# Impedance_analyzer.net
KiCad netlist of a schematic drawn in EAGLE
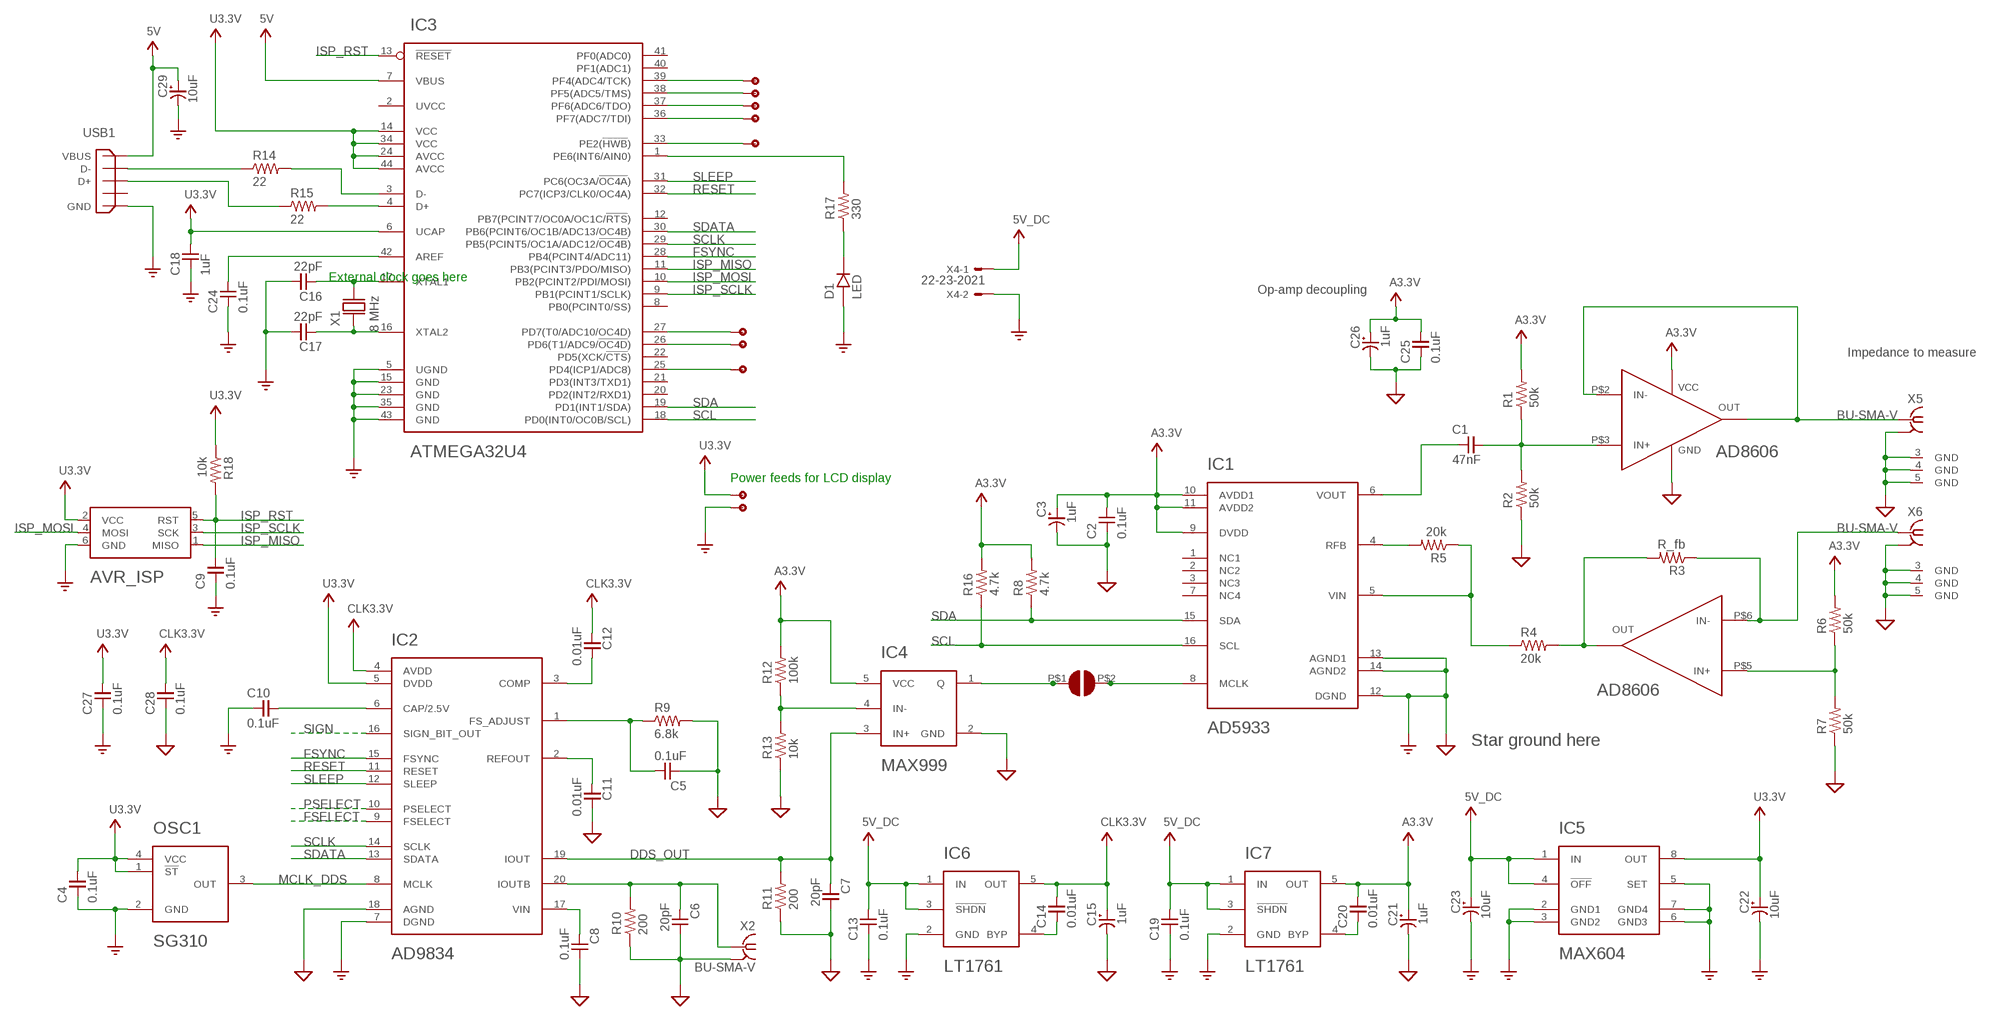
[diagram p0: schematic, sheet 1]

(export (version "E")
  (design (tool "Eeschema 10.0.6"))
  (components
    (comp (ref "C1")
      (value "47nF")
      (footprint "eagle-import:0805")
      (libsource (lib "eagle-import") (part "CAPACITOR0805"))
    )
    (comp (ref "C2")
      (value "0.1uF")
      (footprint "eagle-import:0805")
      (libsource (lib "eagle-import") (part "CAPACITOR0805"))
    )
    (comp (ref "C3")
      (value "1uF")
      (footprint "eagle-import:1206")
      (libsource (lib "eagle-import") (part "CAPACITOR+"))
    )
    (comp (ref "C4")
      (value "0.1uF")
      (footprint "eagle-import:0805")
      (libsource (lib "eagle-import") (part "CAPACITOR0805"))
    )
    (comp (ref "C5")
      (value "0.1uF")
      (footprint "eagle-import:0805")
      (libsource (lib "eagle-import") (part "CAPACITOR0805"))
    )
    (comp (ref "C6")
      (value "20pF")
      (footprint "eagle-import:0805")
      (libsource (lib "eagle-import") (part "CAPACITOR0805"))
    )
    (comp (ref "C7")
      (value "20pF")
      (footprint "eagle-import:0805")
      (libsource (lib "eagle-import") (part "CAPACITOR0805"))
    )
    (comp (ref "C8")
      (value "0.1uF")
      (footprint "eagle-import:0805")
      (libsource (lib "eagle-import") (part "CAPACITOR0805"))
    )
    (comp (ref "C9")
      (value "0.1uF")
      (footprint "eagle-import:0805")
      (libsource (lib "eagle-import") (part "CAPACITOR0805"))
    )
    (comp (ref "C10")
      (value "0.1uF")
      (footprint "eagle-import:0805")
      (libsource (lib "eagle-import") (part "CAPACITOR0805"))
    )
    (comp (ref "C11")
      (value "0.01uF")
      (footprint "eagle-import:0805")
      (libsource (lib "eagle-import") (part "CAPACITOR0805"))
    )
    (comp (ref "C12")
      (value "0.01uF")
      (footprint "eagle-import:0805")
      (libsource (lib "eagle-import") (part "CAPACITOR0805"))
    )
    (comp (ref "C13")
      (value "0.1uF")
      (footprint "eagle-import:0805")
      (libsource (lib "eagle-import") (part "CAPACITOR0805"))
    )
    (comp (ref "C14")
      (value "0.01uF")
      (footprint "eagle-import:0805")
      (libsource (lib "eagle-import") (part "CAPACITOR0805"))
    )
    (comp (ref "C15")
      (value "1uF")
      (footprint "eagle-import:1206")
      (libsource (lib "eagle-import") (part "CAPACITOR+"))
    )
    (comp (ref "C16")
      (value "22pF")
      (footprint "eagle-import:0805")
      (libsource (lib "eagle-import") (part "CAPACITOR0805"))
    )
    (comp (ref "C17")
      (value "22pF")
      (footprint "eagle-import:0805")
      (libsource (lib "eagle-import") (part "CAPACITOR0805"))
    )
    (comp (ref "C18")
      (value "1uF")
      (footprint "eagle-import:0805")
      (libsource (lib "eagle-import") (part "CAPACITOR0805"))
    )
    (comp (ref "C19")
      (value "0.1uF")
      (footprint "eagle-import:0805")
      (libsource (lib "eagle-import") (part "CAPACITOR0805"))
    )
    (comp (ref "C20")
      (value "0.01uF")
      (footprint "eagle-import:0805")
      (libsource (lib "eagle-import") (part "CAPACITOR0805"))
    )
    (comp (ref "C21")
      (value "1uF")
      (footprint "eagle-import:1206")
      (libsource (lib "eagle-import") (part "CAPACITOR+"))
    )
    (comp (ref "C22")
      (value "10uF")
      (footprint "eagle-import:1206")
      (libsource (lib "eagle-import") (part "CAPACITOR+"))
    )
    (comp (ref "C23")
      (value "10uF")
      (footprint "eagle-import:1206")
      (libsource (lib "eagle-import") (part "CAPACITOR+"))
    )
    (comp (ref "C24")
      (value "0.1uF")
      (footprint "eagle-import:0805")
      (libsource (lib "eagle-import") (part "CAPACITOR0805"))
    )
    (comp (ref "C25")
      (value "0.1uF")
      (footprint "eagle-import:0805")
      (libsource (lib "eagle-import") (part "CAPACITOR0805"))
    )
    (comp (ref "C26")
      (value "1uF")
      (footprint "eagle-import:1206")
      (libsource (lib "eagle-import") (part "CAPACITOR+"))
    )
    (comp (ref "C27")
      (value "0.1uF")
      (footprint "eagle-import:0805")
      (libsource (lib "eagle-import") (part "CAPACITOR0805"))
    )
    (comp (ref "C28")
      (value "0.1uF")
      (footprint "eagle-import:0805")
      (libsource (lib "eagle-import") (part "CAPACITOR0805"))
    )
    (comp (ref "C29")
      (value "10uF")
      (footprint "eagle-import:1206")
      (libsource (lib "eagle-import") (part "CAPACITOR+"))
    )
    (comp (ref "D1")
      (value "LED")
      (footprint "eagle-import:0805")
      (libsource (lib "eagle-import") (part "DIODE0805"))
    )
    (comp (ref "IC1")
      (value "AD5933")
      (footprint "eagle-import:SSOP_16")
      (libsource (lib "eagle-import") (part "AD5933"))
    )
    (comp (ref "IC2")
      (value "AD9834")
      (footprint "eagle-import:TSSOP_20")
      (libsource (lib "eagle-import") (part "AD9834"))
    )
    (comp (ref "IC3")
      (value "ATMEGA32U4")
      (footprint "eagle-import:TQFP_44")
      (libsource (lib "eagle-import") (part "ATMEGA32U4"))
    )
    (comp (ref "IC4")
      (value "MAX999")
      (footprint "eagle-import:SOT_23-5")
      (libsource (lib "eagle-import") (part "MAX999"))
    )
    (comp (ref "IC5")
      (value "MAX604")
      (footprint "eagle-import:SO_8")
      (libsource (lib "eagle-import") (part "MAX603"))
    )
    (comp (ref "IC6")
      (value "LT1761")
      (footprint "eagle-import:TSOT-23")
      (libsource (lib "eagle-import") (part "LT1761"))
    )
    (comp (ref "IC7")
      (value "LT1761")
      (footprint "eagle-import:TSOT-23")
      (libsource (lib "eagle-import") (part "LT1761"))
    )
    (comp (ref "IC8")
      (value "AD8606")
      (footprint "eagle-import:MSOP_8")
      (libsource (lib "eagle-import") (part "AD8606"))
    )
    (comp (ref "OSC1")
      (value "SG310")
      (footprint "eagle-import:SG310")
      (libsource (lib "eagle-import") (part "SG310"))
    )
    (comp (ref "R1")
      (value "50k")
      (footprint "eagle-import:0805")
      (libsource (lib "eagle-import") (part "RESISTOR0805SMD"))
    )
    (comp (ref "R2")
      (value "50k")
      (footprint "eagle-import:0805")
      (libsource (lib "eagle-import") (part "RESISTOR0805SMD"))
    )
    (comp (ref "R3")
      (value "R_fb")
      (footprint "eagle-import:0805")
      (libsource (lib "eagle-import") (part "RESISTOR0805SMD"))
    )
    (comp (ref "R4")
      (value "20k")
      (footprint "eagle-import:0805")
      (libsource (lib "eagle-import") (part "RESISTOR0805SMD"))
    )
    (comp (ref "R5")
      (value "20k")
      (footprint "eagle-import:0805")
      (libsource (lib "eagle-import") (part "RESISTOR0805SMD"))
    )
    (comp (ref "R6")
      (value "50k")
      (footprint "eagle-import:0805")
      (libsource (lib "eagle-import") (part "RESISTOR0805SMD"))
    )
    (comp (ref "R7")
      (value "50k")
      (footprint "eagle-import:0805")
      (libsource (lib "eagle-import") (part "RESISTOR0805SMD"))
    )
    (comp (ref "R8")
      (value "4.7k")
      (footprint "eagle-import:0805")
      (libsource (lib "eagle-import") (part "RESISTOR0805SMD"))
    )
    (comp (ref "R9")
      (value "6.8k")
      (footprint "eagle-import:0805")
      (libsource (lib "eagle-import") (part "RESISTOR0805SMD"))
    )
    (comp (ref "R10")
      (value "200")
      (footprint "eagle-import:0805")
      (libsource (lib "eagle-import") (part "RESISTOR0805SMD"))
    )
    (comp (ref "R11")
      (value "200")
      (footprint "eagle-import:0805")
      (libsource (lib "eagle-import") (part "RESISTOR0805SMD"))
    )
    (comp (ref "R12")
      (value "100k")
      (footprint "eagle-import:0805")
      (libsource (lib "eagle-import") (part "RESISTOR0805SMD"))
    )
    (comp (ref "R13")
      (value "10k")
      (footprint "eagle-import:0805")
      (libsource (lib "eagle-import") (part "RESISTOR0805SMD"))
    )
    (comp (ref "R14")
      (value "22")
      (footprint "eagle-import:0805")
      (libsource (lib "eagle-import") (part "RESISTOR0805SMD"))
    )
    (comp (ref "R15")
      (value "22")
      (footprint "eagle-import:0805")
      (libsource (lib "eagle-import") (part "RESISTOR0805SMD"))
    )
    (comp (ref "R16")
      (value "4.7k")
      (footprint "eagle-import:0805")
      (libsource (lib "eagle-import") (part "RESISTOR0805SMD"))
    )
    (comp (ref "R17")
      (value "330")
      (footprint "eagle-import:0805")
      (libsource (lib "eagle-import") (part "RESISTOR0805SMD"))
    )
    (comp (ref "R18")
      (value "10k")
      (footprint "eagle-import:0805")
      (libsource (lib "eagle-import") (part "RESISTOR0805SMD"))
    )
    (comp (ref "TP1")
      (value "TPSMALL")
      (footprint "eagle-import:TP_SMALL")
      (libsource (lib "eagle-import") (part "TPSMALL"))
    )
    (comp (ref "TP2")
      (value "TPSMALL")
      (footprint "eagle-import:TP_SMALL")
      (libsource (lib "eagle-import") (part "TPSMALL"))
    )
    (comp (ref "TP3")
      (value "TPSMALL")
      (footprint "eagle-import:TP_SMALL")
      (libsource (lib "eagle-import") (part "TPSMALL"))
    )
    (comp (ref "TP4")
      (value "TPSMALL")
      (footprint "eagle-import:TP_SMALL")
      (libsource (lib "eagle-import") (part "TPSMALL"))
    )
    (comp (ref "TP5")
      (value "TPSMALL")
      (footprint "eagle-import:TP_SMALL")
      (libsource (lib "eagle-import") (part "TPSMALL"))
    )
    (comp (ref "TP6")
      (value "TPSMALL")
      (footprint "eagle-import:TP_SMALL")
      (libsource (lib "eagle-import") (part "TPSMALL"))
    )
    (comp (ref "TP7")
      (value "TPSMALL")
      (footprint "eagle-import:TP_SMALL")
      (libsource (lib "eagle-import") (part "TPSMALL"))
    )
    (comp (ref "TP10")
      (value "TPSMALL")
      (footprint "eagle-import:TP_SMALL")
      (libsource (lib "eagle-import") (part "TPSMALL"))
    )
    (comp (ref "TP11")
      (value "TPSMALL")
      (footprint "eagle-import:TP_SMALL")
      (libsource (lib "eagle-import") (part "TPSMALL"))
    )
    (comp (ref "TP12")
      (value "TPSMALL")
      (footprint "eagle-import:TP_SMALL")
      (libsource (lib "eagle-import") (part "TPSMALL"))
    )
    (comp (ref "U$41")
      (value "ISP_HEADER")
      (footprint "eagle-import:ISP_HEADER")
      (libsource (lib "eagle-import") (part "ISP_HEADER"))
    )
    (comp (ref "U$57")
      (value "JUMPER")
      (footprint "eagle-import:JUMPER")
      (libsource (lib "eagle-import") (part "JUMPER"))
    )
    (comp (ref "USB1")
      (value "USB_MINIUX60-MB-5ST")
      (footprint "eagle-import:USB_MINI")
      (libsource (lib "eagle-import") (part "USB_MINIUX60-MB-5ST"))
    )
    (comp (ref "X1")
      (value "8 MHz")
      (footprint "eagle-import:NX5032")
      (libsource (lib "eagle-import") (part "CRYSTALNX5032"))
    )
    (comp (ref "X2")
      (value "BU-SMA-V")
      (footprint "eagle-import:BU-SMA-V")
      (fields (field (name "OC_FARNELL") "unknown") (field (name "OC_NEWARK") "unknown"))
      (libsource (lib "eagle-import") (part "BU-SMA-V"))
    )
    (comp (ref "X4")
      (value "22-23-2021")
      (footprint "eagle-import:22-23-2021")
      (fields (field (name "MF") "MOLEX"))
      (libsource (lib "eagle-import") (part "22-23-2021"))
    )
    (comp (ref "X5")
      (value "BU-SMA-V")
      (footprint "eagle-import:BU-SMA-V")
      (fields (field (name "OC_FARNELL") "unknown") (field (name "OC_NEWARK") "unknown"))
      (libsource (lib "eagle-import") (part "BU-SMA-V"))
    )
    (comp (ref "X6")
      (value "BU-SMA-V")
      (footprint "eagle-import:BU-SMA-V")
      (fields (field (name "OC_FARNELL") "unknown") (field (name "OC_NEWARK") "unknown"))
      (libsource (lib "eagle-import") (part "BU-SMA-V"))
    )
  )
  (nets
    (net (code "1") (name "/DDS_OUT") (class "Default")
      (node (ref "C7") (pin "1") (pinfunction "1_1") (pintype "passive"))
      (node (ref "IC2") (pin "19") (pinfunction "IOUT_19") (pintype "bidirectional"))
      (node (ref "IC4") (pin "3") (pinfunction "IN+_3") (pintype "bidirectional"))
      (node (ref "R11") (pin "2") (pinfunction "2_2") (pintype "passive"))
    )
    (net (code "2") (name "/FSELECT") (class "Default")
      (node (ref "IC2") (pin "9") (pinfunction "FSELECT_9") (pintype "bidirectional"))
    )
    (net (code "3") (name "/FSYNC") (class "Default")
      (node (ref "IC2") (pin "15") (pinfunction "FSYNC_15") (pintype "bidirectional"))
      (node (ref "IC3") (pin "28") (pinfunction "PB4(PCINT4/ADC11)_28") (pintype "bidirectional"))
    )
    (net (code "4") (name "/ISP_MISO") (class "Default")
      (node (ref "IC3") (pin "11") (pinfunction "PB3(PCINT3/PDO/MISO)_11") (pintype "bidirectional"))
      (node (ref "U$41") (pin "1") (pinfunction "MISO_1") (pintype "bidirectional"))
    )
    (net (code "5") (name "/ISP_MOSI") (class "Default")
      (node (ref "IC3") (pin "10") (pinfunction "PB2(PCINT2/PDI/MOSI)_10") (pintype "bidirectional"))
      (node (ref "U$41") (pin "4") (pinfunction "MOSI_4") (pintype "bidirectional"))
    )
    (net (code "6") (name "/ISP_RST") (class "Default")
      (node (ref "C9") (pin "2") (pinfunction "2_2") (pintype "passive"))
      (node (ref "IC3") (pin "13") (pinfunction "~{RESET}_13") (pintype "bidirectional"))
      (node (ref "R18") (pin "2") (pinfunction "2_2") (pintype "passive"))
      (node (ref "U$41") (pin "5") (pinfunction "RST_5") (pintype "bidirectional"))
    )
    (net (code "7") (name "/ISP_SCLK") (class "Default")
      (node (ref "IC3") (pin "9") (pinfunction "PB1(PCINT1/SCLK)_9") (pintype "bidirectional"))
      (node (ref "U$41") (pin "3") (pinfunction "SCK_3") (pintype "bidirectional"))
    )
    (net (code "8") (name "/MCLK_DDS") (class "Default")
      (node (ref "IC2") (pin "8") (pinfunction "MCLK_8") (pintype "bidirectional"))
      (node (ref "OSC1") (pin "3") (pinfunction "OUT_3") (pintype "bidirectional"))
    )
    (net (code "9") (name "/PSELECT") (class "Default")
      (node (ref "IC2") (pin "10") (pinfunction "PSELECT_10") (pintype "bidirectional"))
    )
    (net (code "10") (name "/RESET") (class "Default")
      (node (ref "IC2") (pin "11") (pinfunction "RESET_11") (pintype "bidirectional"))
      (node (ref "IC3") (pin "32") (pinfunction "PC7(ICP3/CLK0/OC4A)_32") (pintype "bidirectional"))
    )
    (net (code "11") (name "/SCL") (class "Default")
      (node (ref "IC1") (pin "16") (pinfunction "SCL_16") (pintype "bidirectional"))
      (node (ref "IC3") (pin "18") (pinfunction "PD0(INT0/OC0B/SCL)_18") (pintype "bidirectional"))
      (node (ref "R16") (pin "1") (pinfunction "1_1") (pintype "passive"))
    )
    (net (code "12") (name "/SCLK") (class "Default")
      (node (ref "IC2") (pin "14") (pinfunction "SCLK_14") (pintype "bidirectional"))
      (node (ref "IC3") (pin "29") (pinfunction "PB5(PCINT5/OC1A/ADC12/~{OC4B})_29") (pintype "bidirectional"))
    )
    (net (code "13") (name "/SDA") (class "Default")
      (node (ref "IC1") (pin "15") (pinfunction "SDA_15") (pintype "bidirectional"))
      (node (ref "IC3") (pin "19") (pinfunction "PD1(INT1/SDA)_19") (pintype "bidirectional"))
      (node (ref "R8") (pin "1") (pinfunction "1_1") (pintype "passive"))
    )
    (net (code "14") (name "/SDATA") (class "Default")
      (node (ref "IC2") (pin "13") (pinfunction "SDATA_13") (pintype "bidirectional"))
      (node (ref "IC3") (pin "30") (pinfunction "PB6(PCINT6/OC1B/ADC13/OC4B)_30") (pintype "bidirectional"))
    )
    (net (code "15") (name "/SIGN") (class "Default")
      (node (ref "IC2") (pin "16") (pinfunction "SIGN_BIT_OUT_16") (pintype "bidirectional"))
    )
    (net (code "16") (name "/SLEEP") (class "Default")
      (node (ref "IC2") (pin "12") (pinfunction "SLEEP_12") (pintype "bidirectional"))
      (node (ref "IC3") (pin "31") (pinfunction "PC6(OC3A/~{OC4A})_31") (pintype "bidirectional"))
    )
    (net (code "17") (name "5V") (class "Default")
      (node (ref "C29") (pin "1") (pinfunction "1_1") (pintype "passive"))
      (node (ref "IC3") (pin "7") (pinfunction "VBUS_7") (pintype "bidirectional"))
      (node (ref "USB1") (pin "1") (pinfunction "VBUS_1") (pintype "input"))
    )
    (net (code "18") (name "5V_DC") (class "Default")
      (node (ref "C13") (pin "2") (pinfunction "2_2") (pintype "passive"))
      (node (ref "C19") (pin "2") (pinfunction "2_2") (pintype "passive"))
      (node (ref "C23") (pin "1") (pinfunction "1_1") (pintype "passive"))
      (node (ref "IC5") (pin "1") (pinfunction "IN_1") (pintype "bidirectional"))
      (node (ref "IC5") (pin "4") (pinfunction "~{OFF}_4") (pintype "bidirectional"))
      (node (ref "IC6") (pin "1") (pinfunction "IN_1") (pintype "bidirectional"))
      (node (ref "IC6") (pin "3") (pinfunction "~{SHDN}_3") (pintype "bidirectional"))
      (node (ref "IC7") (pin "1") (pinfunction "IN_1") (pintype "bidirectional"))
      (node (ref "IC7") (pin "3") (pinfunction "~{SHDN}_3") (pintype "bidirectional"))
      (node (ref "X4") (pin "1") (pinfunction "S_1") (pintype "passive"))
    )
    (net (code "19") (name "A3.3V") (class "Default")
      (node (ref "C2") (pin "2") (pinfunction "2_2") (pintype "passive"))
      (node (ref "C20") (pin "2") (pinfunction "2_2") (pintype "passive"))
      (node (ref "C21") (pin "1") (pinfunction "1_1") (pintype "passive"))
      (node (ref "C25") (pin "2") (pinfunction "2_2") (pintype "passive"))
      (node (ref "C26") (pin "1") (pinfunction "1_1") (pintype "passive"))
      (node (ref "C3") (pin "1") (pinfunction "1_1") (pintype "passive"))
      (node (ref "IC1") (pin "10") (pinfunction "AVDD1_10") (pintype "bidirectional"))
      (node (ref "IC1") (pin "11") (pinfunction "AVDD2_11") (pintype "bidirectional"))
      (node (ref "IC1") (pin "9") (pinfunction "DVDD_9") (pintype "bidirectional"))
      (node (ref "IC4") (pin "5") (pinfunction "VCC_5") (pintype "bidirectional"))
      (node (ref "IC7") (pin "5") (pinfunction "OUT_5") (pintype "bidirectional"))
      (node (ref "IC8") (pin "P$8") (pinfunction "VCC_P$8") (pintype "bidirectional"))
      (node (ref "R1") (pin "2") (pinfunction "2_2") (pintype "passive"))
      (node (ref "R12") (pin "2") (pinfunction "2_2") (pintype "passive"))
      (node (ref "R16") (pin "2") (pinfunction "2_2") (pintype "passive"))
      (node (ref "R6") (pin "2") (pinfunction "2_2") (pintype "passive"))
      (node (ref "R8") (pin "2") (pinfunction "2_2") (pintype "passive"))
    )
    (net (code "20") (name "AGND") (class "Default")
      (node (ref "C10") (pin "1") (pinfunction "1_1") (pintype "passive"))
      (node (ref "C11") (pin "2") (pinfunction "2_2") (pintype "passive"))
      (node (ref "C13") (pin "1") (pinfunction "1_1") (pintype "passive"))
      (node (ref "C15") (pin "2") (pinfunction "2_2") (pintype "passive"))
      (node (ref "C16") (pin "2") (pinfunction "2_2") (pintype "passive"))
      (node (ref "C17") (pin "2") (pinfunction "2_2") (pintype "passive"))
      (node (ref "C18") (pin "1") (pinfunction "1_1") (pintype "passive"))
      (node (ref "C19") (pin "1") (pinfunction "1_1") (pintype "passive"))
      (node (ref "C2") (pin "1") (pinfunction "1_1") (pintype "passive"))
      (node (ref "C21") (pin "2") (pinfunction "2_2") (pintype "passive"))
      (node (ref "C22") (pin "2") (pinfunction "2_2") (pintype "passive"))
      (node (ref "C23") (pin "2") (pinfunction "2_2") (pintype "passive"))
      (node (ref "C24") (pin "1") (pinfunction "1_1") (pintype "passive"))
      (node (ref "C25") (pin "1") (pinfunction "1_1") (pintype "passive"))
      (node (ref "C26") (pin "2") (pinfunction "2_2") (pintype "passive"))
      (node (ref "C27") (pin "1") (pinfunction "1_1") (pintype "passive"))
      (node (ref "C28") (pin "1") (pinfunction "1_1") (pintype "passive"))
      (node (ref "C29") (pin "2") (pinfunction "2_2") (pintype "passive"))
      (node (ref "C3") (pin "2") (pinfunction "2_2") (pintype "passive"))
      (node (ref "C4") (pin "1") (pinfunction "1_1") (pintype "passive"))
      (node (ref "C5") (pin "1") (pinfunction "1_1") (pintype "passive"))
      (node (ref "C6") (pin "2") (pinfunction "2_2") (pintype "passive"))
      (node (ref "C7") (pin "2") (pinfunction "2_2") (pintype "passive"))
      (node (ref "C8") (pin "2") (pinfunction "2_2") (pintype "passive"))
      (node (ref "C9") (pin "1") (pinfunction "1_1") (pintype "passive"))
      (node (ref "D1") (pin "1") (pinfunction "A_1") (pintype "bidirectional"))
      (node (ref "IC1") (pin "12") (pinfunction "DGND_12") (pintype "bidirectional"))
      (node (ref "IC1") (pin "13") (pinfunction "AGND1_13") (pintype "bidirectional"))
      (node (ref "IC1") (pin "14") (pinfunction "AGND2_14") (pintype "bidirectional"))
      (node (ref "IC2") (pin "18") (pinfunction "AGND_18") (pintype "bidirectional"))
      (node (ref "IC2") (pin "7") (pinfunction "DGND_7") (pintype "bidirectional"))
      (node (ref "IC3") (pin "15") (pinfunction "GND_15") (pintype "bidirectional"))
      (node (ref "IC3") (pin "23") (pinfunction "GND_23") (pintype "bidirectional"))
      (node (ref "IC3") (pin "35") (pinfunction "GND_35") (pintype "bidirectional"))
      (node (ref "IC3") (pin "43") (pinfunction "GND_43") (pintype "bidirectional"))
      (node (ref "IC3") (pin "5") (pinfunction "UGND_5") (pintype "bidirectional"))
      (node (ref "IC4") (pin "2") (pinfunction "GND_2") (pintype "bidirectional"))
      (node (ref "IC5") (pin "2") (pinfunction "GND1_2") (pintype "bidirectional"))
      (node (ref "IC5") (pin "3") (pinfunction "GND2_3") (pintype "bidirectional"))
      (node (ref "IC5") (pin "5") (pinfunction "SET_5") (pintype "bidirectional"))
      (node (ref "IC5") (pin "6") (pinfunction "GND3_6") (pintype "bidirectional"))
      (node (ref "IC5") (pin "7") (pinfunction "GND4_7") (pintype "bidirectional"))
      (node (ref "IC6") (pin "2") (pinfunction "GND_2") (pintype "bidirectional"))
      (node (ref "IC7") (pin "2") (pinfunction "GND_2") (pintype "bidirectional"))
      (node (ref "IC8") (pin "P$4") (pinfunction "GND_P$4") (pintype "bidirectional"))
      (node (ref "OSC1") (pin "2") (pinfunction "GND_2") (pintype "bidirectional"))
      (node (ref "R10") (pin "1") (pinfunction "1_1") (pintype "passive"))
      (node (ref "R11") (pin "1") (pinfunction "1_1") (pintype "passive"))
      (node (ref "R13") (pin "1") (pinfunction "1_1") (pintype "passive"))
      (node (ref "R2") (pin "1") (pinfunction "1_1") (pintype "passive"))
      (node (ref "R7") (pin "1") (pinfunction "1_1") (pintype "passive"))
      (node (ref "R9") (pin "2") (pinfunction "2_2") (pintype "passive"))
      (node (ref "TP11") (pin "TP_SMALL") (pinfunction "P$1_TP_SMALL") (pintype "bidirectional"))
      (node (ref "U$41") (pin "6") (pinfunction "GND_6") (pintype "bidirectional"))
      (node (ref "USB1") (pin "5") (pinfunction "GND_5") (pintype "input"))
      (node (ref "X2") (pin "2") (pinfunction "GND_2") (pintype "power_in"))
      (node (ref "X4") (pin "2") (pinfunction "S_2") (pintype "passive"))
      (node (ref "X5") (pin "2") (pinfunction "GND_2") (pintype "power_in"))
      (node (ref "X5") (pin "3") (pinfunction "GND_3") (pintype "power_in"))
      (node (ref "X5") (pin "4") (pinfunction "GND_4") (pintype "power_in"))
      (node (ref "X5") (pin "5") (pinfunction "GND_5") (pintype "power_in"))
      (node (ref "X6") (pin "2") (pinfunction "GND_2") (pintype "power_in"))
      (node (ref "X6") (pin "3") (pinfunction "GND_3") (pintype "power_in"))
      (node (ref "X6") (pin "4") (pinfunction "GND_4") (pintype "power_in"))
      (node (ref "X6") (pin "5") (pinfunction "GND_5") (pintype "power_in"))
    )
    (net (code "21") (name "CLK3.3V") (class "Default")
      (node (ref "C12") (pin "1") (pinfunction "1_1") (pintype "passive"))
      (node (ref "C14") (pin "2") (pinfunction "2_2") (pintype "passive"))
      (node (ref "C15") (pin "1") (pinfunction "1_1") (pintype "passive"))
      (node (ref "C28") (pin "2") (pinfunction "2_2") (pintype "passive"))
      (node (ref "IC2") (pin "4") (pinfunction "AVDD_4") (pintype "bidirectional"))
      (node (ref "IC6") (pin "5") (pinfunction "OUT_5") (pintype "bidirectional"))
    )
    (net (code "22") (name "Net-(D1-K)") (class "Default")
      (node (ref "D1") (pin "2") (pinfunction "K_2") (pintype "bidirectional"))
      (node (ref "R17") (pin "1") (pinfunction "1_1") (pintype "passive"))
    )
    (net (code "23") (name "Net-(IC1-MCLK)") (class "Default")
      (node (ref "IC1") (pin "8") (pinfunction "MCLK_8") (pintype "bidirectional"))
      (node (ref "U$57") (pin "P$2") (pinfunction "P$2_P$2") (pintype "bidirectional"))
    )
    (net (code "24") (name "Net-(IC1-RFB)") (class "Default")
      (node (ref "IC1") (pin "4") (pinfunction "RFB_4") (pintype "bidirectional"))
      (node (ref "R5") (pin "2") (pinfunction "2_2") (pintype "passive"))
    )
    (net (code "25") (name "Net-(IC1-VIN)") (class "Default")
      (node (ref "IC1") (pin "5") (pinfunction "VIN_5") (pintype "bidirectional"))
      (node (ref "R4") (pin "1") (pinfunction "1_1") (pintype "passive"))
      (node (ref "R5") (pin "1") (pinfunction "1_1") (pintype "passive"))
    )
    (net (code "26") (name "Net-(IC1-VOUT)") (class "Default")
      (node (ref "C1") (pin "1") (pinfunction "1_1") (pintype "passive"))
      (node (ref "IC1") (pin "6") (pinfunction "VOUT_6") (pintype "bidirectional"))
    )
    (net (code "27") (name "Net-(IC2-CAP{slash}2.5V)") (class "Default")
      (node (ref "C10") (pin "2") (pinfunction "2_2") (pintype "passive"))
      (node (ref "IC2") (pin "6") (pinfunction "CAP/2.5V_6") (pintype "bidirectional"))
    )
    (net (code "28") (name "Net-(IC2-COMP)") (class "Default")
      (node (ref "C12") (pin "2") (pinfunction "2_2") (pintype "passive"))
      (node (ref "IC2") (pin "3") (pinfunction "COMP_3") (pintype "bidirectional"))
    )
    (net (code "29") (name "Net-(IC2-FS_ADJUST)") (class "Default")
      (node (ref "C5") (pin "2") (pinfunction "2_2") (pintype "passive"))
      (node (ref "IC2") (pin "1") (pinfunction "FS_ADJUST_1") (pintype "bidirectional"))
      (node (ref "R9") (pin "1") (pinfunction "1_1") (pintype "passive"))
    )
    (net (code "30") (name "Net-(IC2-IOUTB)") (class "Default")
      (node (ref "C6") (pin "1") (pinfunction "1_1") (pintype "passive"))
      (node (ref "IC2") (pin "20") (pinfunction "IOUTB_20") (pintype "bidirectional"))
      (node (ref "R10") (pin "2") (pinfunction "2_2") (pintype "passive"))
      (node (ref "X2") (pin "1") (pinfunction "1_1") (pintype "passive"))
    )
    (net (code "31") (name "Net-(IC2-REFOUT)") (class "Default")
      (node (ref "C11") (pin "1") (pinfunction "1_1") (pintype "passive"))
      (node (ref "IC2") (pin "2") (pinfunction "REFOUT_2") (pintype "bidirectional"))
    )
    (net (code "32") (name "Net-(IC2-VIN)") (class "Default")
      (node (ref "C8") (pin "1") (pinfunction "1_1") (pintype "passive"))
      (node (ref "IC2") (pin "17") (pinfunction "VIN_17") (pintype "bidirectional"))
    )
    (net (code "33") (name "Net-(IC3-AREF)") (class "Default")
      (node (ref "C24") (pin "2") (pinfunction "2_2") (pintype "passive"))
      (node (ref "IC3") (pin "42") (pinfunction "AREF_42") (pintype "bidirectional"))
    )
    (net (code "34") (name "Net-(IC3-D+)") (class "Default")
      (node (ref "IC3") (pin "4") (pinfunction "D+_4") (pintype "bidirectional"))
      (node (ref "R15") (pin "2") (pinfunction "2_2") (pintype "passive"))
    )
    (net (code "35") (name "Net-(IC3-D-)") (class "Default")
      (node (ref "IC3") (pin "3") (pinfunction "D-_3") (pintype "bidirectional"))
      (node (ref "R14") (pin "2") (pinfunction "2_2") (pintype "passive"))
    )
    (net (code "36") (name "Net-(IC3-PD4(ICP1{slash}ADC8))") (class "Default")
      (node (ref "IC3") (pin "25") (pinfunction "PD4(ICP1/ADC8)_25") (pintype "bidirectional"))
      (node (ref "TP7") (pin "TP_SMALL") (pinfunction "P$1_TP_SMALL") (pintype "bidirectional"))
    )
    (net (code "37") (name "Net-(IC3-PD6(T1{slash}ADC9{slash}~{OC4D}))") (class "Default")
      (node (ref "IC3") (pin "26") (pinfunction "PD6(T1/ADC9/~{OC4D})_26") (pintype "bidirectional"))
      (node (ref "TP2") (pin "TP_SMALL") (pinfunction "P$1_TP_SMALL") (pintype "bidirectional"))
    )
    (net (code "38") (name "Net-(IC3-PD7(T0{slash}ADC10{slash}OC4D))") (class "Default")
      (node (ref "IC3") (pin "27") (pinfunction "PD7(T0/ADC10/OC4D)_27") (pintype "bidirectional"))
      (node (ref "TP1") (pin "TP_SMALL") (pinfunction "P$1_TP_SMALL") (pintype "bidirectional"))
    )
    (net (code "39") (name "Net-(IC3-PE2(~{HWB}))") (class "Default")
      (node (ref "IC3") (pin "33") (pinfunction "PE2(~{HWB})_33") (pintype "bidirectional"))
      (node (ref "TP12") (pin "TP_SMALL") (pinfunction "P$1_TP_SMALL") (pintype "bidirectional"))
    )
    (net (code "40") (name "Net-(IC3-PE6(INT6{slash}AIN0))") (class "Default")
      (node (ref "IC3") (pin "1") (pinfunction "PE6(INT6/AIN0)_1") (pintype "bidirectional"))
      (node (ref "R17") (pin "2") (pinfunction "2_2") (pintype "passive"))
    )
    (net (code "41") (name "Net-(IC3-PF4(ADC4{slash}TCK))") (class "Default")
      (node (ref "IC3") (pin "39") (pinfunction "PF4(ADC4/TCK)_39") (pintype "bidirectional"))
      (node (ref "TP3") (pin "TP_SMALL") (pinfunction "P$1_TP_SMALL") (pintype "bidirectional"))
    )
    (net (code "42") (name "Net-(IC3-PF5(ADC5{slash}TMS))") (class "Default")
      (node (ref "IC3") (pin "38") (pinfunction "PF5(ADC5/TMS)_38") (pintype "bidirectional"))
      (node (ref "TP4") (pin "TP_SMALL") (pinfunction "P$1_TP_SMALL") (pintype "bidirectional"))
    )
    (net (code "43") (name "Net-(IC3-PF6(ADC6{slash}TDO))") (class "Default")
      (node (ref "IC3") (pin "37") (pinfunction "PF6(ADC6/TDO)_37") (pintype "bidirectional"))
      (node (ref "TP5") (pin "TP_SMALL") (pinfunction "P$1_TP_SMALL") (pintype "bidirectional"))
    )
    (net (code "44") (name "Net-(IC3-PF7(ADC7{slash}TDI))") (class "Default")
      (node (ref "IC3") (pin "36") (pinfunction "PF7(ADC7/TDI)_36") (pintype "bidirectional"))
      (node (ref "TP6") (pin "TP_SMALL") (pinfunction "P$1_TP_SMALL") (pintype "bidirectional"))
    )
    (net (code "45") (name "Net-(IC3-XTAL1)") (class "Default")
      (node (ref "C16") (pin "1") (pinfunction "1_1") (pintype "passive"))
      (node (ref "IC3") (pin "17") (pinfunction "XTAL1_17") (pintype "bidirectional"))
      (node (ref "X1") (pin "P$2") (pinfunction "2_P$2") (pintype "bidirectional"))
    )
    (net (code "46") (name "Net-(IC3-XTAL2)") (class "Default")
      (node (ref "C17") (pin "1") (pinfunction "1_1") (pintype "passive"))
      (node (ref "IC3") (pin "16") (pinfunction "XTAL2_16") (pintype "bidirectional"))
      (node (ref "X1") (pin "P$1") (pinfunction "1_P$1") (pintype "bidirectional"))
    )
    (net (code "47") (name "Net-(IC4-IN-)") (class "Default")
      (node (ref "IC4") (pin "4") (pinfunction "IN-_4") (pintype "bidirectional"))
      (node (ref "R12") (pin "1") (pinfunction "1_1") (pintype "passive"))
      (node (ref "R13") (pin "2") (pinfunction "2_2") (pintype "passive"))
    )
    (net (code "48") (name "Net-(IC4-Q)") (class "Default")
      (node (ref "IC4") (pin "1") (pinfunction "Q_1") (pintype "bidirectional"))
      (node (ref "U$57") (pin "P$1") (pinfunction "P$1_P$1") (pintype "bidirectional"))
    )
    (net (code "49") (name "Net-(IC6-BYP)") (class "Default")
      (node (ref "C14") (pin "1") (pinfunction "1_1") (pintype "passive"))
      (node (ref "IC6") (pin "4") (pinfunction "BYP_4") (pintype "bidirectional"))
    )
    (net (code "50") (name "Net-(IC7-BYP)") (class "Default")
      (node (ref "C20") (pin "1") (pinfunction "1_1") (pintype "passive"))
      (node (ref "IC7") (pin "4") (pinfunction "BYP_4") (pintype "bidirectional"))
    )
    (net (code "51") (name "Net-(IC8A-IN+)") (class "Default")
      (node (ref "C1") (pin "2") (pinfunction "2_2") (pintype "passive"))
      (node (ref "IC8") (pin "P$3") (pinfunction "IN+_P$3") (pintype "bidirectional"))
      (node (ref "R1") (pin "1") (pinfunction "1_1") (pintype "passive"))
      (node (ref "R2") (pin "2") (pinfunction "2_2") (pintype "passive"))
    )
    (net (code "52") (name "Net-(IC8A-IN-)") (class "Default")
      (node (ref "IC8") (pin "P$1") (pinfunction "OUT_P$1") (pintype "bidirectional"))
      (node (ref "IC8") (pin "P$2") (pinfunction "IN-_P$2") (pintype "bidirectional"))
      (node (ref "X5") (pin "1") (pinfunction "1_1") (pintype "passive"))
    )
    (net (code "53") (name "Net-(IC8B-IN+)") (class "Default")
      (node (ref "IC8") (pin "P$5") (pinfunction "IN+_P$5") (pintype "bidirectional"))
      (node (ref "R6") (pin "1") (pinfunction "1_1") (pintype "passive"))
      (node (ref "R7") (pin "2") (pinfunction "2_2") (pintype "passive"))
    )
    (net (code "54") (name "Net-(IC8B-IN-)") (class "Default")
      (node (ref "IC8") (pin "P$6") (pinfunction "IN-_P$6") (pintype "bidirectional"))
      (node (ref "R3") (pin "1") (pinfunction "1_1") (pintype "passive"))
      (node (ref "X6") (pin "1") (pinfunction "1_1") (pintype "passive"))
    )
    (net (code "55") (name "Net-(IC8B-OUT)") (class "Default")
      (node (ref "IC8") (pin "P$7") (pinfunction "OUT_P$7") (pintype "bidirectional"))
      (node (ref "R3") (pin "2") (pinfunction "2_2") (pintype "passive"))
      (node (ref "R4") (pin "2") (pinfunction "2_2") (pintype "passive"))
    )
    (net (code "56") (name "Net-(USB1-D+)") (class "Default")
      (node (ref "R15") (pin "1") (pinfunction "1_1") (pintype "passive"))
      (node (ref "USB1") (pin "3") (pinfunction "D+_3") (pintype "input"))
    )
    (net (code "57") (name "Net-(USB1-D-)") (class "Default")
      (node (ref "R14") (pin "1") (pinfunction "1_1") (pintype "passive"))
      (node (ref "USB1") (pin "2") (pinfunction "D-_2") (pintype "input"))
    )
    (net (code "58") (name "U3.3V") (class "Default")
      (node (ref "C18") (pin "2") (pinfunction "2_2") (pintype "passive"))
      (node (ref "C22") (pin "1") (pinfunction "1_1") (pintype "passive"))
      (node (ref "C27") (pin "2") (pinfunction "2_2") (pintype "passive"))
      (node (ref "C4") (pin "2") (pinfunction "2_2") (pintype "passive"))
      (node (ref "IC2") (pin "5") (pinfunction "DVDD_5") (pintype "bidirectional"))
      (node (ref "IC3") (pin "14") (pinfunction "VCC_14") (pintype "bidirectional"))
      (node (ref "IC3") (pin "24") (pinfunction "AVCC_24") (pintype "bidirectional"))
      (node (ref "IC3") (pin "34") (pinfunction "VCC_34") (pintype "bidirectional"))
      (node (ref "IC3") (pin "44") (pinfunction "AVCC_44") (pintype "bidirectional"))
      (node (ref "IC3") (pin "6") (pinfunction "UCAP_6") (pintype "bidirectional"))
      (node (ref "IC5") (pin "8") (pinfunction "OUT_8") (pintype "bidirectional"))
      (node (ref "OSC1") (pin "1") (pinfunction "~{ST}_1") (pintype "bidirectional"))
      (node (ref "OSC1") (pin "4") (pinfunction "VCC_4") (pintype "bidirectional"))
      (node (ref "R18") (pin "1") (pinfunction "1_1") (pintype "passive"))
      (node (ref "TP10") (pin "TP_SMALL") (pinfunction "P$1_TP_SMALL") (pintype "bidirectional"))
      (node (ref "U$41") (pin "2") (pinfunction "VCC_2") (pintype "bidirectional"))
    )
    (net (code "59") (name "unconnected-(IC1-NC1-Pad1)") (class "Default")
      (node (ref "IC1") (pin "1") (pinfunction "NC1_1") (pintype "no_connect"))
    )
    (net (code "60") (name "unconnected-(IC1-NC2-Pad2)") (class "Default")
      (node (ref "IC1") (pin "2") (pinfunction "NC2_2") (pintype "no_connect"))
    )
    (net (code "61") (name "unconnected-(IC1-NC3-Pad3)") (class "Default")
      (node (ref "IC1") (pin "3") (pinfunction "NC3_3") (pintype "no_connect"))
    )
    (net (code "62") (name "unconnected-(IC1-NC4-Pad7)") (class "Default")
      (node (ref "IC1") (pin "7") (pinfunction "NC4_7") (pintype "no_connect"))
    )
    (net (code "63") (name "unconnected-(IC3-PB0(PCINT0{slash}SS)-Pad8)") (class "Default")
      (node (ref "IC3") (pin "8") (pinfunction "PB0(PCINT0/SS)_8") (pintype "bidirectional"))
    )
    (net (code "64") (name "unconnected-(IC3-PB7(PCINT7{slash}OC0A{slash}OC1C{slash}~{RTS})-Pad12)") (class "Default")
      (node (ref "IC3") (pin "12") (pinfunction "PB7(PCINT7/OC0A/OC1C/~{RTS})_12") (pintype "bidirectional"))
    )
    (net (code "65") (name "unconnected-(IC3-PD2(INT2{slash}RXD1)-Pad20)") (class "Default")
      (node (ref "IC3") (pin "20") (pinfunction "PD2(INT2/RXD1)_20") (pintype "bidirectional"))
    )
    (net (code "66") (name "unconnected-(IC3-PD3(INT3{slash}TXD1)-Pad21)") (class "Default")
      (node (ref "IC3") (pin "21") (pinfunction "PD3(INT3/TXD1)_21") (pintype "bidirectional"))
    )
    (net (code "67") (name "unconnected-(IC3-PD5(XCK{slash}~{CTS})-Pad22)") (class "Default")
      (node (ref "IC3") (pin "22") (pinfunction "PD5(XCK/~{CTS})_22") (pintype "bidirectional"))
    )
    (net (code "68") (name "unconnected-(IC3-PF0(ADC0)-Pad41)") (class "Default")
      (node (ref "IC3") (pin "41") (pinfunction "PF0(ADC0)_41") (pintype "bidirectional"))
    )
    (net (code "69") (name "unconnected-(IC3-PF1(ADC1)-Pad40)") (class "Default")
      (node (ref "IC3") (pin "40") (pinfunction "PF1(ADC1)_40") (pintype "bidirectional"))
    )
    (net (code "70") (name "unconnected-(IC3-UVCC-Pad2)") (class "Default")
      (node (ref "IC3") (pin "2") (pinfunction "UVCC_2") (pintype "bidirectional"))
    )
    (net (code "71") (name "unconnected-(USB1-NC-Pad4)") (class "Default")
      (node (ref "USB1") (pin "4") (pinfunction "NC_4") (pintype "no_connect"))
    )
  )
)
